# Light_Sensor.net
KiCad netlist of a schematic drawn in Altium Designer
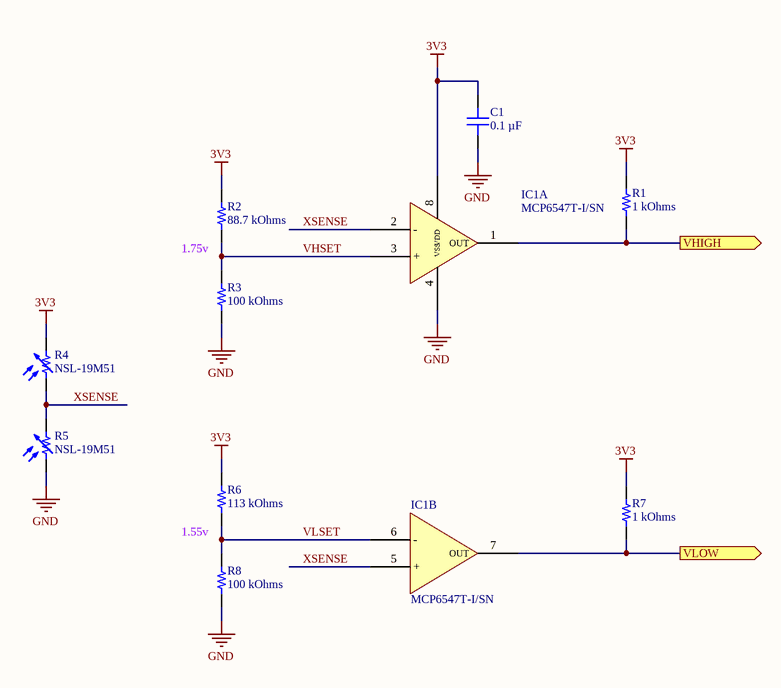
[diagram p0: Light Sensor.SchDoc]

(export (version "E")
  (design (tool "Eeschema 10.0.6"))
  (components
    (comp (ref "C1")
      (value "0.1 µF")
      (footprint "CAP 0603_1608")
      (description "CAP CER 0.1UF 50V X7R 0603")
      (fields (field (name "PART NUMBER") "C0603C104K5RAC7411") (field (name "MANUFACTURER") "KEMET"))
      (libsource (lib "altiumlibrary.com") (part "Capacitor"))
    )
    (comp (ref "IC1")
      (value "MCP6547T-I/SN")
      (footprint "MICROCHIP SOIC-8 SN")
      (description "IC COMP OPENDRN 1.6V DUAL 8-SOIC")
      (fields (field (name "MANUFACTURER") "Microchip Technology"))
      (libsource (lib "altiumlibrary.com") (part "MICROCHIP MCP6547T-I SN"))
    )
    (comp (ref "R1")
      (value "1 kOhms")
      (footprint "RES 0603_1608")
      (description "RES SMD 1K OHM 5% 1/4W 0603")
      (fields
        (field (name "PART NUMBER") "ERJ-PA3J102V")
        (field (name "MANUFACTURER") "Panasonic Electronic Components")
      )
      (libsource (lib "altiumlibrary.com") (part "Resistor"))
    )
    (comp (ref "R2")
      (value "88.7 kOhms")
      (footprint "RES 0603_1608")
      (description "RES 88.7K OHM 1% 1/10W 0603")
      (fields (field (name "PART NUMBER") "RC0603FR-0788K7L") (field (name "MANUFACTURER") "Yageo"))
      (libsource (lib "altiumlibrary.com") (part "Resistor"))
    )
    (comp (ref "R3")
      (value "100 kOhms")
      (footprint "RES 0603_1608")
      (description "RES SMD 100K OHM 1% 1/4W 0603")
      (fields
        (field (name "PART NUMBER") "ERJ-PA3F1003V")
        (field (name "MANUFACTURER") "Panasonic Electronic Components")
      )
      (libsource (lib "altiumlibrary.com") (part "Resistor"))
    )
    (comp (ref "R4")
      (value "NSL-19M51")
      (footprint "ADVANCED PHOTONIX NSL-19M51")
      (description "PHOTOCELL")
      (fields (field (name "MANUFACTURER") "Advanced Photonix"))
      (libsource (lib "altiumlibrary.com") (part "PHOTORESISTOR"))
    )
    (comp (ref "R5")
      (value "NSL-19M51")
      (footprint "ADVANCED PHOTONIX NSL-19M51")
      (description "PHOTOCELL")
      (fields (field (name "MANUFACTURER") "Advanced Photonix"))
      (libsource (lib "altiumlibrary.com") (part "PHOTORESISTOR"))
    )
    (comp (ref "R6")
      (value "113 kOhms")
      (footprint "RES 0603_1608")
      (description "RES 113K OHM 1% 1/10W 0603")
      (fields
        (field (name "PART NUMBER") "RMCF0603FT113K")
        (field (name "MANUFACTURER") "Stackpole Electronics Inc")
      )
      (libsource (lib "altiumlibrary.com") (part "Resistor"))
    )
    (comp (ref "R7")
      (value "1 kOhms")
      (footprint "RES 0603_1608")
      (description "RES SMD 1K OHM 5% 1/4W 0603")
      (fields
        (field (name "PART NUMBER") "ERJ-PA3J102V")
        (field (name "MANUFACTURER") "Panasonic Electronic Components")
      )
      (libsource (lib "altiumlibrary.com") (part "Resistor"))
    )
    (comp (ref "R8")
      (value "100 kOhms")
      (footprint "RES 0603_1608")
      (description "RES SMD 100K OHM 1% 1/4W 0603")
      (fields
        (field (name "PART NUMBER") "ERJ-PA3F1003V")
        (field (name "MANUFACTURER") "Panasonic Electronic Components")
      )
      (libsource (lib "altiumlibrary.com") (part "Resistor"))
    )
  )
  (nets
    (net (code "1") (name "/VHIGH") (class "Default")
      (node (ref "IC1") (pin "1") (pinfunction "OUT_1") (pintype "passive"))
      (node (ref "R1") (pin "1") (pinfunction "1_1") (pintype "passive"))
    )
    (net (code "2") (name "/VHSET") (class "Default")
      (node (ref "IC1") (pin "3") (pinfunction "+_3") (pintype "passive"))
      (node (ref "R2") (pin "1") (pinfunction "1_1") (pintype "passive"))
      (node (ref "R3") (pin "2") (pinfunction "2_2") (pintype "passive"))
    )
    (net (code "3") (name "/VLOW") (class "Default")
      (node (ref "IC1") (pin "7") (pinfunction "OUT_7") (pintype "passive"))
      (node (ref "R7") (pin "1") (pinfunction "1_1") (pintype "passive"))
    )
    (net (code "4") (name "/VLSET") (class "Default")
      (node (ref "IC1") (pin "6") (pinfunction "-_6") (pintype "passive"))
      (node (ref "R6") (pin "1") (pinfunction "1_1") (pintype "passive"))
      (node (ref "R8") (pin "2") (pinfunction "2_2") (pintype "passive"))
    )
    (net (code "5") (name "/XSENSE") (class "Default")
      (node (ref "IC1") (pin "2") (pinfunction "-_2") (pintype "passive"))
      (node (ref "IC1") (pin "5") (pinfunction "+_5") (pintype "passive"))
      (node (ref "R4") (pin "1") (pinfunction "1_1") (pintype "passive"))
      (node (ref "R5") (pin "2") (pinfunction "2_2") (pintype "passive"))
    )
    (net (code "6") (name "3V3") (class "Default")
      (node (ref "C1") (pin "2") (pinfunction "2_2") (pintype "passive"))
      (node (ref "IC1") (pin "8") (pinfunction "VDD_8") (pintype "power_in"))
      (node (ref "R1") (pin "2") (pinfunction "2_2") (pintype "passive"))
      (node (ref "R2") (pin "2") (pinfunction "2_2") (pintype "passive"))
      (node (ref "R4") (pin "2") (pinfunction "2_2") (pintype "passive"))
      (node (ref "R6") (pin "2") (pinfunction "2_2") (pintype "passive"))
      (node (ref "R7") (pin "2") (pinfunction "2_2") (pintype "passive"))
    )
    (net (code "7") (name "GND") (class "Default")
      (node (ref "C1") (pin "1") (pinfunction "1_1") (pintype "passive"))
      (node (ref "IC1") (pin "4") (pinfunction "VSS_4") (pintype "power_in"))
      (node (ref "R3") (pin "1") (pinfunction "1_1") (pintype "passive"))
      (node (ref "R5") (pin "1") (pinfunction "1_1") (pintype "passive"))
      (node (ref "R8") (pin "1") (pinfunction "1_1") (pintype "passive"))
    )
  )
)
